# Lazerade_RGB.net
KiCad netlist of a schematic drawn in EAGLE
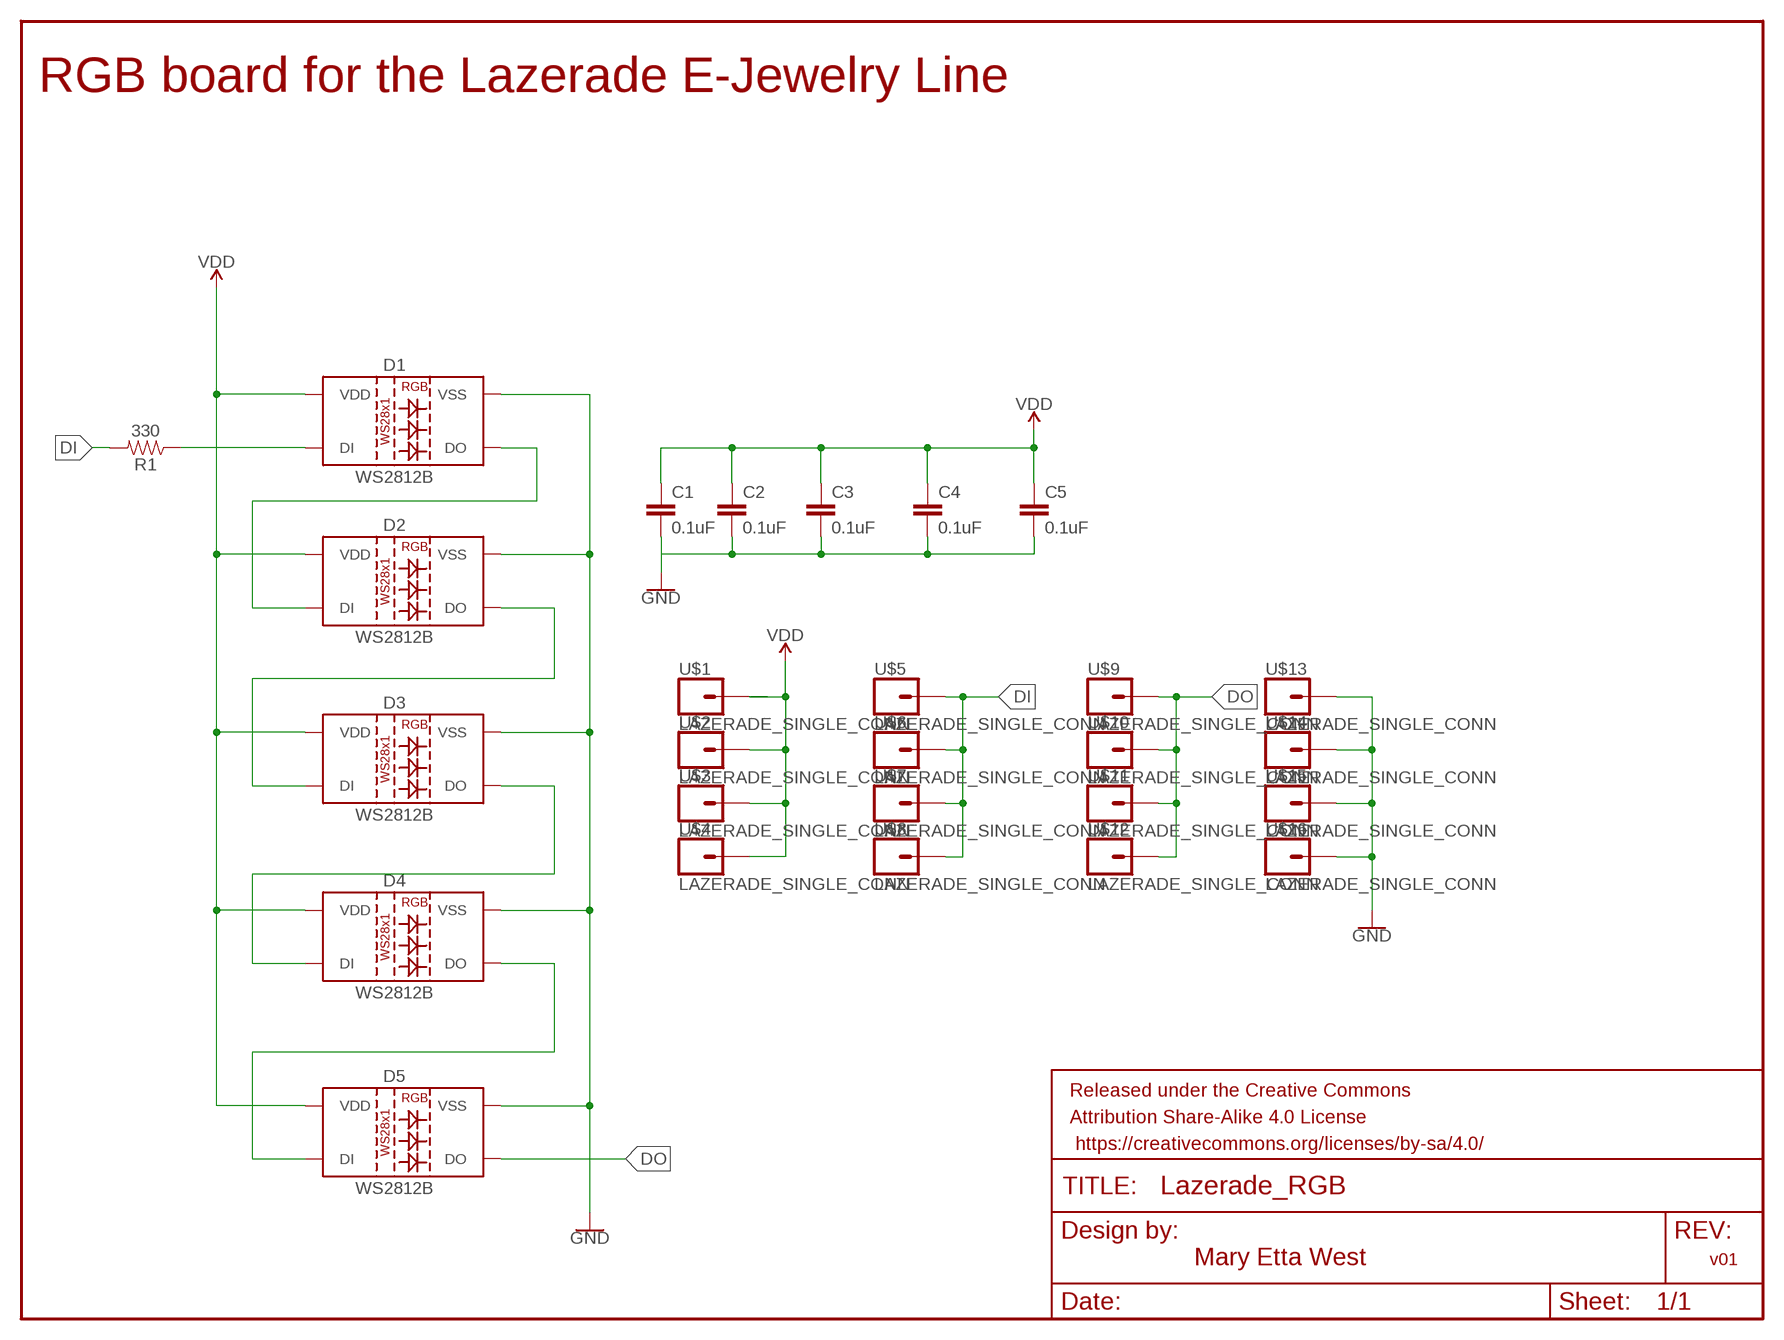
[diagram p0: schematic, sheet 1]

(export (version "E")
  (design (tool "Eeschema 10.0.6"))
  (components
    (comp (ref "C1")
      (value "0.1uF")
      (footprint "eagle-import:0603")
      (libsource (lib "eagle-import") (part "0.1UF-0603-25V-(+80/-20%)"))
    )
    (comp (ref "C2")
      (value "0.1uF")
      (footprint "eagle-import:0603")
      (libsource (lib "eagle-import") (part "0.1UF-0603-25V-(+80/-20%)"))
    )
    (comp (ref "C3")
      (value "0.1uF")
      (footprint "eagle-import:0603")
      (libsource (lib "eagle-import") (part "0.1UF-0603-25V-(+80/-20%)"))
    )
    (comp (ref "C4")
      (value "0.1uF")
      (footprint "eagle-import:0603")
      (libsource (lib "eagle-import") (part "0.1UF-0603-25V-(+80/-20%)"))
    )
    (comp (ref "C5")
      (value "0.1uF")
      (footprint "eagle-import:0603")
      (libsource (lib "eagle-import") (part "0.1UF-0603-25V-(+80/-20%)"))
    )
    (comp (ref "D1")
      (value "WS2812B")
      (footprint "eagle-import:WS2812B")
      (libsource (lib "eagle-import") (part "WS2812B"))
    )
    (comp (ref "D2")
      (value "WS2812B")
      (footprint "eagle-import:WS2812B")
      (libsource (lib "eagle-import") (part "WS2812B"))
    )
    (comp (ref "D3")
      (value "WS2812B")
      (footprint "eagle-import:WS2812B")
      (libsource (lib "eagle-import") (part "WS2812B"))
    )
    (comp (ref "D4")
      (value "WS2812B")
      (footprint "eagle-import:WS2812B")
      (libsource (lib "eagle-import") (part "WS2812B"))
    )
    (comp (ref "D5")
      (value "WS2812B")
      (footprint "eagle-import:WS2812B")
      (libsource (lib "eagle-import") (part "WS2812B"))
    )
    (comp (ref "FRAME1")
      (value "FRAME-LETTER")
      (footprint "eagle-import:CREATIVE_COMMONS")
      (libsource (lib "eagle-import") (part "FRAME-LETTER"))
    )
    (comp (ref "R1")
      (value "330")
      (footprint "eagle-import:0603")
      (libsource (lib "eagle-import") (part "330OHM-0603-1/10W-1%"))
    )
    (comp (ref "U$1")
      (value "LAZERADE_SINGLE_CONN")
      (footprint "eagle-import:SINLGE_PAD_CONNECT")
      (libsource (lib "eagle-import") (part "LAZERADE_SINGLE_CONN"))
    )
    (comp (ref "U$2")
      (value "LAZERADE_SINGLE_CONN")
      (footprint "eagle-import:SINLGE_PAD_CONNECT")
      (libsource (lib "eagle-import") (part "LAZERADE_SINGLE_CONN"))
    )
    (comp (ref "U$3")
      (value "LAZERADE_SINGLE_CONN")
      (footprint "eagle-import:SINLGE_PAD_CONNECT")
      (libsource (lib "eagle-import") (part "LAZERADE_SINGLE_CONN"))
    )
    (comp (ref "U$4")
      (value "LAZERADE_SINGLE_CONN")
      (footprint "eagle-import:SINLGE_PAD_CONNECT")
      (libsource (lib "eagle-import") (part "LAZERADE_SINGLE_CONN"))
    )
    (comp (ref "U$5")
      (value "LAZERADE_SINGLE_CONN")
      (footprint "eagle-import:SINLGE_PAD_CONNECT")
      (libsource (lib "eagle-import") (part "LAZERADE_SINGLE_CONN"))
    )
    (comp (ref "U$6")
      (value "LAZERADE_SINGLE_CONN")
      (footprint "eagle-import:SINLGE_PAD_CONNECT")
      (libsource (lib "eagle-import") (part "LAZERADE_SINGLE_CONN"))
    )
    (comp (ref "U$7")
      (value "LAZERADE_SINGLE_CONN")
      (footprint "eagle-import:SINLGE_PAD_CONNECT")
      (libsource (lib "eagle-import") (part "LAZERADE_SINGLE_CONN"))
    )
    (comp (ref "U$8")
      (value "LAZERADE_SINGLE_CONN")
      (footprint "eagle-import:SINLGE_PAD_CONNECT")
      (libsource (lib "eagle-import") (part "LAZERADE_SINGLE_CONN"))
    )
    (comp (ref "U$9")
      (value "LAZERADE_SINGLE_CONN")
      (footprint "eagle-import:SINLGE_PAD_CONNECT")
      (libsource (lib "eagle-import") (part "LAZERADE_SINGLE_CONN"))
    )
    (comp (ref "U$10")
      (value "LAZERADE_SINGLE_CONN")
      (footprint "eagle-import:SINLGE_PAD_CONNECT")
      (libsource (lib "eagle-import") (part "LAZERADE_SINGLE_CONN"))
    )
    (comp (ref "U$11")
      (value "LAZERADE_SINGLE_CONN")
      (footprint "eagle-import:SINLGE_PAD_CONNECT")
      (libsource (lib "eagle-import") (part "LAZERADE_SINGLE_CONN"))
    )
    (comp (ref "U$12")
      (value "LAZERADE_SINGLE_CONN")
      (footprint "eagle-import:SINLGE_PAD_CONNECT")
      (libsource (lib "eagle-import") (part "LAZERADE_SINGLE_CONN"))
    )
    (comp (ref "U$13")
      (value "LAZERADE_SINGLE_CONN")
      (footprint "eagle-import:SINLGE_PAD_CONNECT")
      (libsource (lib "eagle-import") (part "LAZERADE_SINGLE_CONN"))
    )
    (comp (ref "U$14")
      (value "LAZERADE_SINGLE_CONN")
      (footprint "eagle-import:SINLGE_PAD_CONNECT")
      (libsource (lib "eagle-import") (part "LAZERADE_SINGLE_CONN"))
    )
    (comp (ref "U$15")
      (value "LAZERADE_SINGLE_CONN")
      (footprint "eagle-import:SINLGE_PAD_CONNECT")
      (libsource (lib "eagle-import") (part "LAZERADE_SINGLE_CONN"))
    )
    (comp (ref "U$16")
      (value "LAZERADE_SINGLE_CONN")
      (footprint "eagle-import:SINLGE_PAD_CONNECT")
      (libsource (lib "eagle-import") (part "LAZERADE_SINGLE_CONN"))
    )
  )
  (nets
    (net (code "1") (name "DI") (class "Default")
      (node (ref "R1") (pin "2") (pinfunction "2_2") (pintype "passive"))
      (node (ref "U$5") (pin "P$1") (pinfunction "1_P$1") (pintype "passive"))
      (node (ref "U$6") (pin "P$1") (pinfunction "1_P$1") (pintype "passive"))
      (node (ref "U$7") (pin "P$1") (pinfunction "1_P$1") (pintype "passive"))
      (node (ref "U$8") (pin "P$1") (pinfunction "1_P$1") (pintype "passive"))
    )
    (net (code "2") (name "DO") (class "Default")
      (node (ref "D5") (pin "2") (pinfunction "DO_2") (pintype "bidirectional"))
      (node (ref "U$10") (pin "P$1") (pinfunction "1_P$1") (pintype "passive"))
      (node (ref "U$11") (pin "P$1") (pinfunction "1_P$1") (pintype "passive"))
      (node (ref "U$12") (pin "P$1") (pinfunction "1_P$1") (pintype "passive"))
      (node (ref "U$9") (pin "P$1") (pinfunction "1_P$1") (pintype "passive"))
    )
    (net (code "3") (name "GND") (class "Default")
      (node (ref "C1") (pin "2") (pinfunction "2_2") (pintype "passive"))
      (node (ref "C2") (pin "2") (pinfunction "2_2") (pintype "passive"))
      (node (ref "C3") (pin "2") (pinfunction "2_2") (pintype "passive"))
      (node (ref "C4") (pin "2") (pinfunction "2_2") (pintype "passive"))
      (node (ref "C5") (pin "2") (pinfunction "2_2") (pintype "passive"))
      (node (ref "D1") (pin "3") (pinfunction "VSS_3") (pintype "bidirectional"))
      (node (ref "D2") (pin "3") (pinfunction "VSS_3") (pintype "bidirectional"))
      (node (ref "D3") (pin "3") (pinfunction "VSS_3") (pintype "bidirectional"))
      (node (ref "D4") (pin "3") (pinfunction "VSS_3") (pintype "bidirectional"))
      (node (ref "D5") (pin "3") (pinfunction "VSS_3") (pintype "bidirectional"))
      (node (ref "U$13") (pin "P$1") (pinfunction "1_P$1") (pintype "passive"))
      (node (ref "U$14") (pin "P$1") (pinfunction "1_P$1") (pintype "passive"))
      (node (ref "U$15") (pin "P$1") (pinfunction "1_P$1") (pintype "passive"))
      (node (ref "U$16") (pin "P$1") (pinfunction "1_P$1") (pintype "passive"))
    )
    (net (code "4") (name "Net-(D1-DI)") (class "Default")
      (node (ref "D1") (pin "4") (pinfunction "DI_4") (pintype "bidirectional"))
      (node (ref "R1") (pin "1") (pinfunction "1_1") (pintype "passive"))
    )
    (net (code "5") (name "Net-(D1-DO)") (class "Default")
      (node (ref "D1") (pin "2") (pinfunction "DO_2") (pintype "bidirectional"))
      (node (ref "D2") (pin "4") (pinfunction "DI_4") (pintype "bidirectional"))
    )
    (net (code "6") (name "Net-(D2-DO)") (class "Default")
      (node (ref "D2") (pin "2") (pinfunction "DO_2") (pintype "bidirectional"))
      (node (ref "D3") (pin "4") (pinfunction "DI_4") (pintype "bidirectional"))
    )
    (net (code "7") (name "Net-(D3-DO)") (class "Default")
      (node (ref "D3") (pin "2") (pinfunction "DO_2") (pintype "bidirectional"))
      (node (ref "D4") (pin "4") (pinfunction "DI_4") (pintype "bidirectional"))
    )
    (net (code "8") (name "Net-(D4-DO)") (class "Default")
      (node (ref "D4") (pin "2") (pinfunction "DO_2") (pintype "bidirectional"))
      (node (ref "D5") (pin "4") (pinfunction "DI_4") (pintype "bidirectional"))
    )
    (net (code "9") (name "VDD") (class "Default")
      (node (ref "C1") (pin "1") (pinfunction "1_1") (pintype "passive"))
      (node (ref "C2") (pin "1") (pinfunction "1_1") (pintype "passive"))
      (node (ref "C3") (pin "1") (pinfunction "1_1") (pintype "passive"))
      (node (ref "C4") (pin "1") (pinfunction "1_1") (pintype "passive"))
      (node (ref "C5") (pin "1") (pinfunction "1_1") (pintype "passive"))
      (node (ref "D1") (pin "1") (pinfunction "VDD_1") (pintype "bidirectional"))
      (node (ref "D2") (pin "1") (pinfunction "VDD_1") (pintype "bidirectional"))
      (node (ref "D3") (pin "1") (pinfunction "VDD_1") (pintype "bidirectional"))
      (node (ref "D4") (pin "1") (pinfunction "VDD_1") (pintype "bidirectional"))
      (node (ref "D5") (pin "1") (pinfunction "VDD_1") (pintype "bidirectional"))
      (node (ref "U$1") (pin "P$1") (pinfunction "1_P$1") (pintype "passive"))
      (node (ref "U$2") (pin "P$1") (pinfunction "1_P$1") (pintype "passive"))
      (node (ref "U$3") (pin "P$1") (pinfunction "1_P$1") (pintype "passive"))
      (node (ref "U$4") (pin "P$1") (pinfunction "1_P$1") (pintype "passive"))
    )
  )
)
